# FPGA_Core.net
KiCad netlist of a schematic drawn in Altium Designer
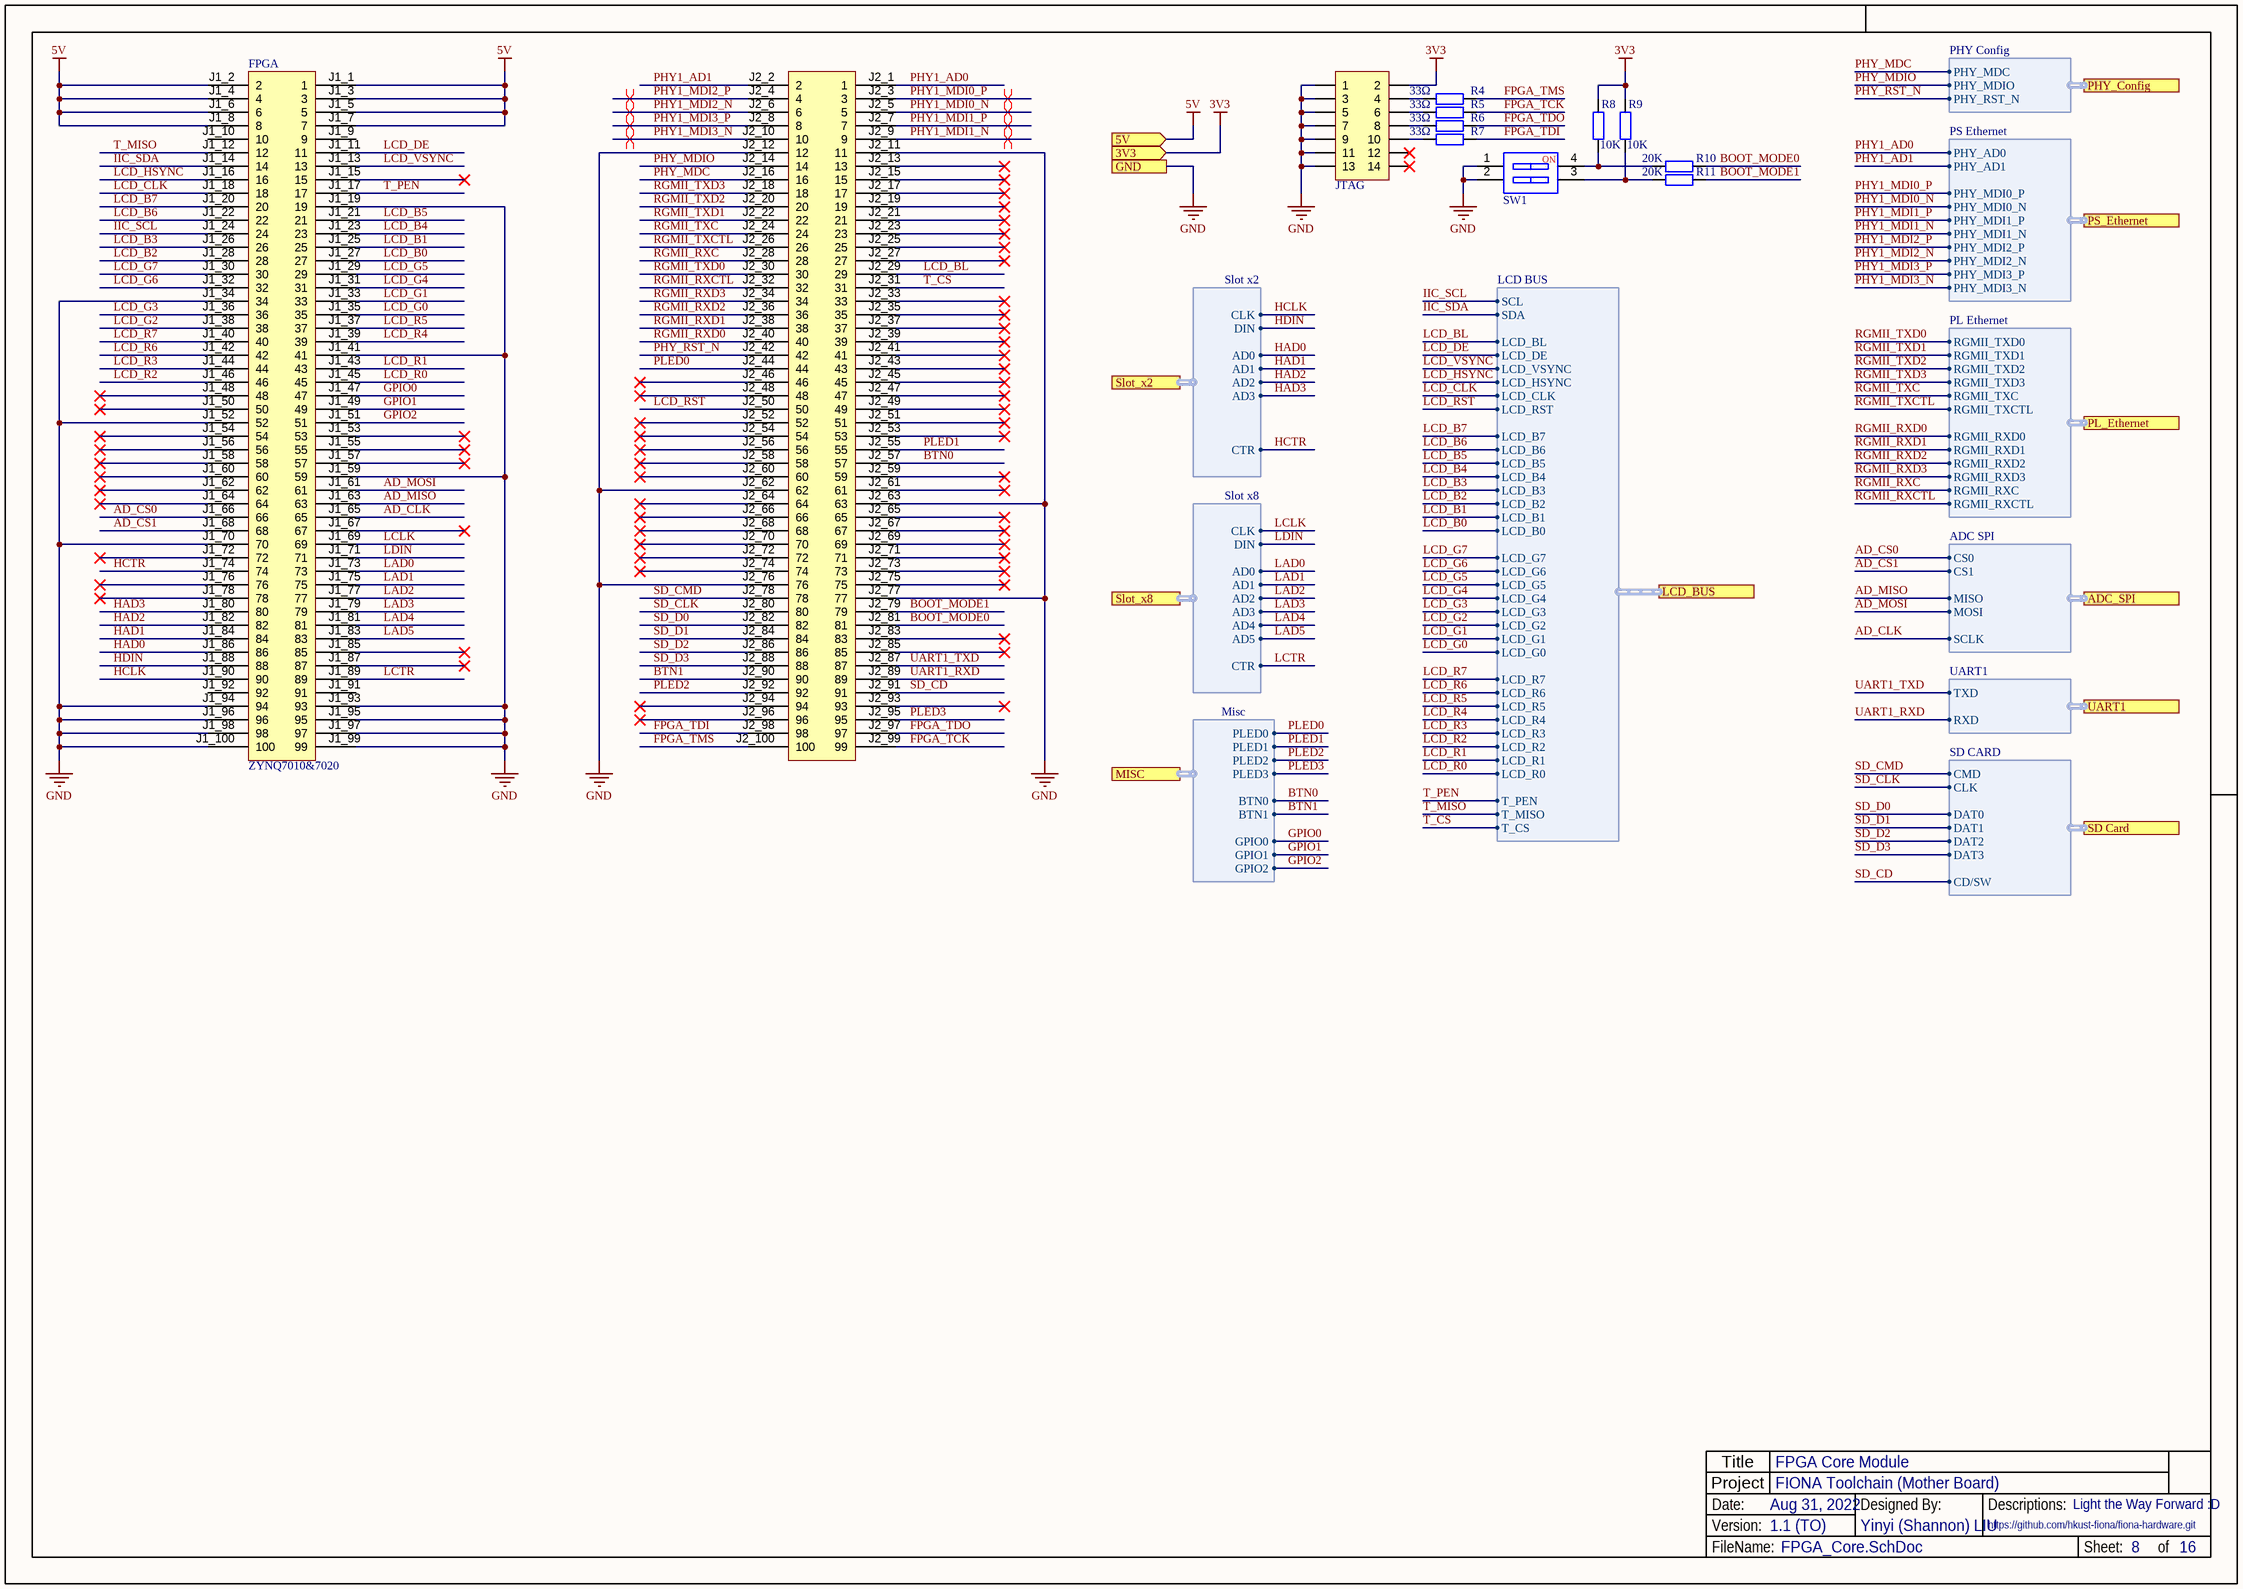
[diagram p0: FPGA_Core.SchDoc]

(export (version "E")
  (design (tool "Eeschema 10.0.6"))
  (components
    (comp (ref "FPGA")
      (value "ZYNQ7010&7020")
      (footprint "ZYNQ7010&7020_CB")
      (description "ZYNQ7010&7020 Core Board")
      (libsource (lib "领航者ZYNQ底板SCH&PCB封装库") (part "ZYNQ7010&7020"))
    )
    (comp (ref "JTAG")
      (value "Header 2X7")
      (footprint "IDC2.54-LI-2x7P")
      (description "7*2P接插件")
      (fields (field (name "版权归属") "封装库来自淘宝 ID：黄晶宝石"))
      (libsource (lib "5.4 - 接插件-脚距2.54 (100mil) ") (part "Header 7X2"))
    )
    (comp (ref "R4")
      (value "33Ω")
      (footprint "R 0603_L")
      (description "贴片电阻")
      (fields (field (name "版权归属") "来自淘宝 ID：黄晶宝石"))
      (libsource (lib "0.1 - 电阻-电容-电感") (part "R"))
    )
    (comp (ref "R5")
      (value "33Ω")
      (footprint "R 0603_L")
      (description "贴片电阻")
      (fields (field (name "版权归属") "来自淘宝 ID：黄晶宝石"))
      (libsource (lib "0.1 - 电阻-电容-电感") (part "R"))
    )
    (comp (ref "R6")
      (value "33Ω")
      (footprint "R 0603_L")
      (description "贴片电阻")
      (fields (field (name "版权归属") "来自淘宝 ID：黄晶宝石"))
      (libsource (lib "0.1 - 电阻-电容-电感") (part "R"))
    )
    (comp (ref "R7")
      (value "33Ω")
      (footprint "R 0603_L")
      (description "贴片电阻")
      (fields (field (name "版权归属") "来自淘宝 ID：黄晶宝石"))
      (libsource (lib "0.1 - 电阻-电容-电感") (part "R"))
    )
    (comp (ref "R8")
      (value "10K")
      (footprint "R 0603_L")
      (description "贴片电阻")
      (fields (field (name "版权归属") "来自淘宝 ID：黄晶宝石"))
      (libsource (lib "0.1 - 电阻-电容-电感") (part "R"))
    )
    (comp (ref "R9")
      (value "10K")
      (footprint "R 0603_L")
      (description "贴片电阻")
      (fields (field (name "版权归属") "来自淘宝 ID：黄晶宝石"))
      (libsource (lib "0.1 - 电阻-电容-电感") (part "R"))
    )
    (comp (ref "R10")
      (value "20K")
      (footprint "R 0603_L")
      (description "贴片电阻")
      (fields (field (name "版权归属") "来自淘宝 ID：黄晶宝石"))
      (libsource (lib "0.1 - 电阻-电容-电感") (part "R"))
    )
    (comp (ref "R11")
      (value "20K")
      (footprint "R 0603_L")
      (description "贴片电阻")
      (fields (field (name "版权归属") "来自淘宝 ID：黄晶宝石"))
      (libsource (lib "0.1 - 电阻-电容-电感") (part "R"))
    )
    (comp (ref "SW1")
      (value "SW-2P")
      (footprint "CSW DIP-2P")
      (description "2路编码开关\r\n*LCID: C976324")
      (libsource (lib "0.7 - 常用按键-开关") (part "SW-2P"))
    )
  )
  (nets
    (net (code "17") (name "/AD_CLK") (class "Default")
      (node (ref "FPGA") (pin "J1_65") (pinfunction "65_J1_65") (pintype "passive"))
    )
    (net (code "18") (name "/AD_CS0") (class "Default")
      (node (ref "FPGA") (pin "J1_66") (pinfunction "66_J1_66") (pintype "passive"))
    )
    (net (code "19") (name "/AD_CS1") (class "Default")
      (node (ref "FPGA") (pin "J1_68") (pinfunction "68_J1_68") (pintype "passive"))
    )
    (net (code "20") (name "/AD_MISO") (class "Default")
      (node (ref "FPGA") (pin "J1_63") (pinfunction "63_J1_63") (pintype "passive"))
    )
    (net (code "21") (name "/AD_MOSI") (class "Default")
      (node (ref "FPGA") (pin "J1_61") (pinfunction "61_J1_61") (pintype "passive"))
    )
    (net (code "22") (name "/BOOT_MODE0") (class "Default")
      (node (ref "FPGA") (pin "J2_81") (pinfunction "81_J2_81") (pintype "passive"))
      (node (ref "R10") (pin "2") (pinfunction "2_2") (pintype "passive"))
    )
    (net (code "23") (name "/BOOT_MODE1") (class "Default")
      (node (ref "FPGA") (pin "J2_79") (pinfunction "79_J2_79") (pintype "passive"))
      (node (ref "R11") (pin "2") (pinfunction "2_2") (pintype "passive"))
    )
    (net (code "24") (name "/BTN0") (class "Default")
      (node (ref "FPGA") (pin "J2_57") (pinfunction "57_J2_57") (pintype "passive"))
    )
    (net (code "25") (name "/BTN1") (class "Default")
      (node (ref "FPGA") (pin "J2_90") (pinfunction "90_J2_90") (pintype "passive"))
    )
    (net (code "26") (name "/FPGA_TCK") (class "Default")
      (node (ref "FPGA") (pin "J2_99") (pinfunction "99_J2_99") (pintype "passive"))
      (node (ref "R5") (pin "2") (pinfunction "2_2") (pintype "passive"))
    )
    (net (code "27") (name "/FPGA_TDI") (class "Default")
      (node (ref "FPGA") (pin "J2_98") (pinfunction "98_J2_98") (pintype "passive"))
      (node (ref "R7") (pin "2") (pinfunction "2_2") (pintype "passive"))
    )
    (net (code "28") (name "/FPGA_TDO") (class "Default")
      (node (ref "FPGA") (pin "J2_97") (pinfunction "97_J2_97") (pintype "passive"))
      (node (ref "R6") (pin "2") (pinfunction "2_2") (pintype "passive"))
    )
    (net (code "29") (name "/FPGA_TMS") (class "Default")
      (node (ref "FPGA") (pin "J2_100") (pinfunction "100_J2_100") (pintype "passive"))
      (node (ref "R4") (pin "2") (pinfunction "2_2") (pintype "passive"))
    )
    (net (code "30") (name "/GPIO0") (class "Default")
      (node (ref "FPGA") (pin "J1_47") (pinfunction "47_J1_47") (pintype "passive"))
    )
    (net (code "31") (name "/GPIO1") (class "Default")
      (node (ref "FPGA") (pin "J1_49") (pinfunction "49_J1_49") (pintype "passive"))
    )
    (net (code "32") (name "/GPIO2") (class "Default")
      (node (ref "FPGA") (pin "J1_51") (pinfunction "51_J1_51") (pintype "passive"))
    )
    (net (code "33") (name "/HAD0") (class "Default")
      (node (ref "FPGA") (pin "J1_86") (pinfunction "86_J1_86") (pintype "passive"))
    )
    (net (code "34") (name "/HAD1") (class "Default")
      (node (ref "FPGA") (pin "J1_84") (pinfunction "84_J1_84") (pintype "passive"))
    )
    (net (code "35") (name "/HAD2") (class "Default")
      (node (ref "FPGA") (pin "J1_82") (pinfunction "82_J1_82") (pintype "passive"))
    )
    (net (code "36") (name "/HAD3") (class "Default")
      (node (ref "FPGA") (pin "J1_80") (pinfunction "80_J1_80") (pintype "passive"))
    )
    (net (code "37") (name "/HCLK") (class "Default")
      (node (ref "FPGA") (pin "J1_90") (pinfunction "90_J1_90") (pintype "passive"))
    )
    (net (code "38") (name "/HCTR") (class "Default")
      (node (ref "FPGA") (pin "J1_74") (pinfunction "74_J1_74") (pintype "passive"))
    )
    (net (code "39") (name "/HDIN") (class "Default")
      (node (ref "FPGA") (pin "J1_88") (pinfunction "88_J1_88") (pintype "passive"))
    )
    (net (code "40") (name "/IIC_SCL") (class "Default")
      (node (ref "FPGA") (pin "J1_24") (pinfunction "24_J1_24") (pintype "passive"))
    )
    (net (code "41") (name "/IIC_SDA") (class "Default")
      (node (ref "FPGA") (pin "J1_14") (pinfunction "14_J1_14") (pintype "passive"))
    )
    (net (code "42") (name "/LAD0") (class "Default")
      (node (ref "FPGA") (pin "J1_73") (pinfunction "73_J1_73") (pintype "passive"))
    )
    (net (code "43") (name "/LAD1") (class "Default")
      (node (ref "FPGA") (pin "J1_75") (pinfunction "75_J1_75") (pintype "passive"))
    )
    (net (code "44") (name "/LAD2") (class "Default")
      (node (ref "FPGA") (pin "J1_77") (pinfunction "77_J1_77") (pintype "passive"))
    )
    (net (code "45") (name "/LAD3") (class "Default")
      (node (ref "FPGA") (pin "J1_79") (pinfunction "79_J1_79") (pintype "passive"))
    )
    (net (code "46") (name "/LAD4") (class "Default")
      (node (ref "FPGA") (pin "J1_81") (pinfunction "81_J1_81") (pintype "passive"))
    )
    (net (code "47") (name "/LAD5") (class "Default")
      (node (ref "FPGA") (pin "J1_83") (pinfunction "83_J1_83") (pintype "passive"))
    )
    (net (code "48") (name "/LCD_B0") (class "Default")
      (node (ref "FPGA") (pin "J1_27") (pinfunction "27_J1_27") (pintype "passive"))
    )
    (net (code "49") (name "/LCD_B1") (class "Default")
      (node (ref "FPGA") (pin "J1_25") (pinfunction "25_J1_25") (pintype "passive"))
    )
    (net (code "50") (name "/LCD_B2") (class "Default")
      (node (ref "FPGA") (pin "J1_28") (pinfunction "28_J1_28") (pintype "passive"))
    )
    (net (code "51") (name "/LCD_B3") (class "Default")
      (node (ref "FPGA") (pin "J1_26") (pinfunction "26_J1_26") (pintype "passive"))
    )
    (net (code "52") (name "/LCD_B4") (class "Default")
      (node (ref "FPGA") (pin "J1_23") (pinfunction "23_J1_23") (pintype "passive"))
    )
    (net (code "53") (name "/LCD_B5") (class "Default")
      (node (ref "FPGA") (pin "J1_21") (pinfunction "21_J1_21") (pintype "passive"))
    )
    (net (code "54") (name "/LCD_B6") (class "Default")
      (node (ref "FPGA") (pin "J1_22") (pinfunction "22_J1_22") (pintype "passive"))
    )
    (net (code "55") (name "/LCD_B7") (class "Default")
      (node (ref "FPGA") (pin "J1_20") (pinfunction "20_J1_20") (pintype "passive"))
    )
    (net (code "56") (name "/LCD_BL") (class "Default")
      (node (ref "FPGA") (pin "J2_29") (pinfunction "29_J2_29") (pintype "passive"))
    )
    (net (code "57") (name "/LCD_CLK") (class "Default")
      (node (ref "FPGA") (pin "J1_18") (pinfunction "18_J1_18") (pintype "passive"))
    )
    (net (code "58") (name "/LCD_DE") (class "Default")
      (node (ref "FPGA") (pin "J1_11") (pinfunction "11_J1_11") (pintype "passive"))
    )
    (net (code "59") (name "/LCD_G0") (class "Default")
      (node (ref "FPGA") (pin "J1_35") (pinfunction "35_J1_35") (pintype "passive"))
    )
    (net (code "60") (name "/LCD_G1") (class "Default")
      (node (ref "FPGA") (pin "J1_33") (pinfunction "33_J1_33") (pintype "passive"))
    )
    (net (code "61") (name "/LCD_G2") (class "Default")
      (node (ref "FPGA") (pin "J1_38") (pinfunction "38_J1_38") (pintype "passive"))
    )
    (net (code "62") (name "/LCD_G3") (class "Default")
      (node (ref "FPGA") (pin "J1_36") (pinfunction "36_J1_36") (pintype "passive"))
    )
    (net (code "63") (name "/LCD_G4") (class "Default")
      (node (ref "FPGA") (pin "J1_31") (pinfunction "31_J1_31") (pintype "passive"))
    )
    (net (code "64") (name "/LCD_G5") (class "Default")
      (node (ref "FPGA") (pin "J1_29") (pinfunction "29_J1_29") (pintype "passive"))
    )
    (net (code "65") (name "/LCD_G6") (class "Default")
      (node (ref "FPGA") (pin "J1_32") (pinfunction "32_J1_32") (pintype "passive"))
    )
    (net (code "66") (name "/LCD_G7") (class "Default")
      (node (ref "FPGA") (pin "J1_30") (pinfunction "30_J1_30") (pintype "passive"))
    )
    (net (code "67") (name "/LCD_HSYNC") (class "Default")
      (node (ref "FPGA") (pin "J1_16") (pinfunction "16_J1_16") (pintype "passive"))
    )
    (net (code "68") (name "/LCD_R0") (class "Default")
      (node (ref "FPGA") (pin "J1_45") (pinfunction "45_J1_45") (pintype "passive"))
    )
    (net (code "69") (name "/LCD_R1") (class "Default")
      (node (ref "FPGA") (pin "J1_43") (pinfunction "43_J1_43") (pintype "passive"))
    )
    (net (code "70") (name "/LCD_R2") (class "Default")
      (node (ref "FPGA") (pin "J1_46") (pinfunction "46_J1_46") (pintype "passive"))
    )
    (net (code "71") (name "/LCD_R3") (class "Default")
      (node (ref "FPGA") (pin "J1_44") (pinfunction "44_J1_44") (pintype "passive"))
    )
    (net (code "72") (name "/LCD_R4") (class "Default")
      (node (ref "FPGA") (pin "J1_39") (pinfunction "39_J1_39") (pintype "passive"))
    )
    (net (code "73") (name "/LCD_R5") (class "Default")
      (node (ref "FPGA") (pin "J1_37") (pinfunction "37_J1_37") (pintype "passive"))
    )
    (net (code "74") (name "/LCD_R6") (class "Default")
      (node (ref "FPGA") (pin "J1_42") (pinfunction "42_J1_42") (pintype "passive"))
    )
    (net (code "75") (name "/LCD_R7") (class "Default")
      (node (ref "FPGA") (pin "J1_40") (pinfunction "40_J1_40") (pintype "passive"))
    )
    (net (code "76") (name "/LCD_RST") (class "Default")
      (node (ref "FPGA") (pin "J2_50") (pinfunction "50_J2_50") (pintype "passive"))
    )
    (net (code "77") (name "/LCD_VSYNC") (class "Default")
      (node (ref "FPGA") (pin "J1_13") (pinfunction "13_J1_13") (pintype "passive"))
    )
    (net (code "78") (name "/LCLK") (class "Default")
      (node (ref "FPGA") (pin "J1_69") (pinfunction "69_J1_69") (pintype "passive"))
    )
    (net (code "79") (name "/LCTR") (class "Default")
      (node (ref "FPGA") (pin "J1_89") (pinfunction "89_J1_89") (pintype "passive"))
    )
    (net (code "80") (name "/LDIN") (class "Default")
      (node (ref "FPGA") (pin "J1_71") (pinfunction "71_J1_71") (pintype "passive"))
    )
    (net (code "81") (name "/PHY1_AD0") (class "Default")
      (node (ref "FPGA") (pin "J2_1") (pinfunction "1_J2_1") (pintype "passive"))
    )
    (net (code "82") (name "/PHY1_AD1") (class "Default")
      (node (ref "FPGA") (pin "J2_2") (pinfunction "2_J2_2") (pintype "passive"))
    )
    (net (code "83") (name "/PHY1_MDI0_N") (class "Default")
      (node (ref "FPGA") (pin "J2_5") (pinfunction "5_J2_5") (pintype "passive"))
    )
    (net (code "84") (name "/PHY1_MDI0_P") (class "Default")
      (node (ref "FPGA") (pin "J2_3") (pinfunction "3_J2_3") (pintype "passive"))
    )
    (net (code "85") (name "/PHY1_MDI1_N") (class "Default")
      (node (ref "FPGA") (pin "J2_9") (pinfunction "9_J2_9") (pintype "passive"))
    )
    (net (code "86") (name "/PHY1_MDI1_P") (class "Default")
      (node (ref "FPGA") (pin "J2_7") (pinfunction "7_J2_7") (pintype "passive"))
    )
    (net (code "87") (name "/PHY1_MDI2_N") (class "Default")
      (node (ref "FPGA") (pin "J2_6") (pinfunction "6_J2_6") (pintype "passive"))
    )
    (net (code "88") (name "/PHY1_MDI2_P") (class "Default")
      (node (ref "FPGA") (pin "J2_4") (pinfunction "4_J2_4") (pintype "passive"))
    )
    (net (code "89") (name "/PHY1_MDI3_N") (class "Default")
      (node (ref "FPGA") (pin "J2_10") (pinfunction "10_J2_10") (pintype "passive"))
    )
    (net (code "90") (name "/PHY1_MDI3_P") (class "Default")
      (node (ref "FPGA") (pin "J2_8") (pinfunction "8_J2_8") (pintype "passive"))
    )
    (net (code "91") (name "/PHY_MDC") (class "Default")
      (node (ref "FPGA") (pin "J2_16") (pinfunction "16_J2_16") (pintype "passive"))
    )
    (net (code "92") (name "/PHY_MDIO") (class "Default")
      (node (ref "FPGA") (pin "J2_14") (pinfunction "14_J2_14") (pintype "passive"))
    )
    (net (code "93") (name "/PHY_RST_N") (class "Default")
      (node (ref "FPGA") (pin "J2_42") (pinfunction "42_J2_42") (pintype "passive"))
    )
    (net (code "94") (name "/PLED0") (class "Default")
      (node (ref "FPGA") (pin "J2_44") (pinfunction "44_J2_44") (pintype "passive"))
    )
    (net (code "95") (name "/PLED1") (class "Default")
      (node (ref "FPGA") (pin "J2_55") (pinfunction "55_J2_55") (pintype "passive"))
    )
    (net (code "96") (name "/PLED2") (class "Default")
      (node (ref "FPGA") (pin "J2_92") (pinfunction "92_J2_92") (pintype "passive"))
    )
    (net (code "97") (name "/PLED3") (class "Default")
      (node (ref "FPGA") (pin "J2_95") (pinfunction "95_J2_95") (pintype "passive"))
    )
    (net (code "98") (name "/RGMII_RXC") (class "Default")
      (node (ref "FPGA") (pin "J2_28") (pinfunction "28_J2_28") (pintype "passive"))
    )
    (net (code "99") (name "/RGMII_RXCTL") (class "Default")
      (node (ref "FPGA") (pin "J2_32") (pinfunction "32_J2_32") (pintype "passive"))
    )
    (net (code "100") (name "/RGMII_RXD0") (class "Default")
      (node (ref "FPGA") (pin "J2_40") (pinfunction "40_J2_40") (pintype "passive"))
    )
    (net (code "101") (name "/RGMII_RXD1") (class "Default")
      (node (ref "FPGA") (pin "J2_38") (pinfunction "38_J2_38") (pintype "passive"))
    )
    (net (code "102") (name "/RGMII_RXD2") (class "Default")
      (node (ref "FPGA") (pin "J2_36") (pinfunction "36_J2_36") (pintype "passive"))
    )
    (net (code "103") (name "/RGMII_RXD3") (class "Default")
      (node (ref "FPGA") (pin "J2_34") (pinfunction "34_J2_34") (pintype "passive"))
    )
    (net (code "104") (name "/RGMII_TXC") (class "Default")
      (node (ref "FPGA") (pin "J2_24") (pinfunction "24_J2_24") (pintype "passive"))
    )
    (net (code "105") (name "/RGMII_TXCTL") (class "Default")
      (node (ref "FPGA") (pin "J2_26") (pinfunction "26_J2_26") (pintype "passive"))
    )
    (net (code "106") (name "/RGMII_TXD0") (class "Default")
      (node (ref "FPGA") (pin "J2_30") (pinfunction "30_J2_30") (pintype "passive"))
    )
    (net (code "107") (name "/RGMII_TXD1") (class "Default")
      (node (ref "FPGA") (pin "J2_22") (pinfunction "22_J2_22") (pintype "passive"))
    )
    (net (code "108") (name "/RGMII_TXD2") (class "Default")
      (node (ref "FPGA") (pin "J2_20") (pinfunction "20_J2_20") (pintype "passive"))
    )
    (net (code "109") (name "/RGMII_TXD3") (class "Default")
      (node (ref "FPGA") (pin "J2_18") (pinfunction "18_J2_18") (pintype "passive"))
    )
    (net (code "110") (name "/SD_CD") (class "Default")
      (node (ref "FPGA") (pin "J2_91") (pinfunction "91_J2_91") (pintype "passive"))
    )
    (net (code "111") (name "/SD_CLK") (class "Default")
      (node (ref "FPGA") (pin "J2_80") (pinfunction "80_J2_80") (pintype "passive"))
    )
    (net (code "112") (name "/SD_CMD") (class "Default")
      (node (ref "FPGA") (pin "J2_78") (pinfunction "78_J2_78") (pintype "passive"))
    )
    (net (code "113") (name "/SD_D0") (class "Default")
      (node (ref "FPGA") (pin "J2_82") (pinfunction "82_J2_82") (pintype "passive"))
    )
    (net (code "114") (name "/SD_D1") (class "Default")
      (node (ref "FPGA") (pin "J2_84") (pinfunction "84_J2_84") (pintype "passive"))
    )
    (net (code "115") (name "/SD_D2") (class "Default")
      (node (ref "FPGA") (pin "J2_86") (pinfunction "86_J2_86") (pintype "passive"))
    )
    (net (code "116") (name "/SD_D3") (class "Default")
      (node (ref "FPGA") (pin "J2_88") (pinfunction "88_J2_88") (pintype "passive"))
    )
    (net (code "117") (name "/T_CS") (class "Default")
      (node (ref "FPGA") (pin "J2_31") (pinfunction "31_J2_31") (pintype "passive"))
    )
    (net (code "118") (name "/T_MISO") (class "Default")
      (node (ref "FPGA") (pin "J1_12") (pinfunction "12_J1_12") (pintype "passive"))
    )
    (net (code "119") (name "/T_PEN") (class "Default")
      (node (ref "FPGA") (pin "J1_17") (pinfunction "17_J1_17") (pintype "passive"))
    )
    (net (code "120") (name "/UART1_RXD") (class "Default")
      (node (ref "FPGA") (pin "J2_89") (pinfunction "89_J2_89") (pintype "passive"))
    )
    (net (code "121") (name "/UART1_TXD") (class "Default")
      (node (ref "FPGA") (pin "J2_87") (pinfunction "87_J2_87") (pintype "passive"))
    )
    (net (code "132") (name "3V3") (class "Default")
      (node (ref "JTAG") (pin "2") (pinfunction "2_2") (pintype "passive"))
      (node (ref "R8") (pin "2") (pinfunction "2_2") (pintype "passive"))
      (node (ref "R9") (pin "2") (pinfunction "2_2") (pintype "passive"))
    )
    (net (code "133") (name "5V") (class "Default")
      (node (ref "FPGA") (pin "J1_1") (pinfunction "1_J1_1") (pintype "passive"))
      (node (ref "FPGA") (pin "J1_2") (pinfunction "2_J1_2") (pintype "passive"))
      (node (ref "FPGA") (pin "J1_3") (pinfunction "3_J1_3") (pintype "passive"))
      (node (ref "FPGA") (pin "J1_4") (pinfunction "4_J1_4") (pintype "passive"))
      (node (ref "FPGA") (pin "J1_5") (pinfunction "5_J1_5") (pintype "passive"))
      (node (ref "FPGA") (pin "J1_6") (pinfunction "6_J1_6") (pintype "passive"))
      (node (ref "FPGA") (pin "J1_7") (pinfunction "7_J1_7") (pintype "passive"))
      (node (ref "FPGA") (pin "J1_8") (pinfunction "8_J1_8") (pintype "passive"))
    )
    (net (code "134") (name "GND") (class "Default")
      (node (ref "FPGA") (pin "J1_100") (pinfunction "100_J1_100") (pintype "passive"))
      (node (ref "FPGA") (pin "J1_19") (pinfunction "19_J1_19") (pintype "passive"))
      (node (ref "FPGA") (pin "J1_34") (pinfunction "34_J1_34") (pintype "passive"))
      (node (ref "FPGA") (pin "J1_41") (pinfunction "41_J1_41") (pintype "passive"))
      (node (ref "FPGA") (pin "J1_52") (pinfunction "52_J1_52") (pintype "passive"))
      (node (ref "FPGA") (pin "J1_59") (pinfunction "59_J1_59") (pintype "passive"))
      (node (ref "FPGA") (pin "J1_70") (pinfunction "70_J1_70") (pintype "passive"))
      (node (ref "FPGA") (pin "J1_93") (pinfunction "93_J1_93") (pintype "passive"))
      (node (ref "FPGA") (pin "J1_94") (pinfunction "94_J1_94") (pintype "passive"))
      (node (ref "FPGA") (pin "J1_95") (pinfunction "95_J1_95") (pintype "passive"))
      (node (ref "FPGA") (pin "J1_96") (pinfunction "96_J1_96") (pintype "passive"))
      (node (ref "FPGA") (pin "J1_97") (pinfunction "97_J1_97") (pintype "passive"))
      (node (ref "FPGA") (pin "J1_98") (pinfunction "98_J1_98") (pintype "passive"))
      (node (ref "FPGA") (pin "J1_99") (pinfunction "99_J1_99") (pintype "passive"))
      (node (ref "FPGA") (pin "J2_11") (pinfunction "11_J2_11") (pintype "passive"))
      (node (ref "FPGA") (pin "J2_12") (pinfunction "12_J2_12") (pintype "passive"))
      (node (ref "FPGA") (pin "J2_62") (pinfunction "62_J2_62") (pintype "passive"))
      (node (ref "FPGA") (pin "J2_63") (pinfunction "63_J2_63") (pintype "passive"))
      (node (ref "FPGA") (pin "J2_76") (pinfunction "76_J2_76") (pintype "passive"))
      (node (ref "FPGA") (pin "J2_77") (pinfunction "77_J2_77") (pintype "passive"))
      (node (ref "JTAG") (pin "1") (pinfunction "1_1") (pintype "passive"))
      (node (ref "JTAG") (pin "11") (pinfunction "11_11") (pintype "passive"))
      (node (ref "JTAG") (pin "13") (pinfunction "13_13") (pintype "passive"))
      (node (ref "JTAG") (pin "3") (pinfunction "3_3") (pintype "passive"))
      (node (ref "JTAG") (pin "5") (pinfunction "5_5") (pintype "passive"))
      (node (ref "JTAG") (pin "7") (pinfunction "7_7") (pintype "passive"))
      (node (ref "JTAG") (pin "9") (pinfunction "9_9") (pintype "passive"))
      (node (ref "SW1") (pin "1") (pinfunction "1_1") (pintype "passive"))
      (node (ref "SW1") (pin "2") (pinfunction "2_2") (pintype "passive"))
    )
    (net (code "135") (name "Net-(JTAG-Pad4)") (class "Default")
      (node (ref "JTAG") (pin "4") (pinfunction "4_4") (pintype "passive"))
      (node (ref "R4") (pin "1") (pinfunction "1_1") (pintype "passive"))
    )
    (net (code "136") (name "Net-(JTAG-Pad6)") (class "Default")
      (node (ref "JTAG") (pin "6") (pinfunction "6_6") (pintype "passive"))
      (node (ref "R5") (pin "1") (pinfunction "1_1") (pintype "passive"))
    )
    (net (code "137") (name "Net-(JTAG-Pad8)") (class "Default")
      (node (ref "JTAG") (pin "8") (pinfunction "8_8") (pintype "passive"))
      (node (ref "R6") (pin "1") (pinfunction "1_1") (pintype "passive"))
    )
    (net (code "138") (name "Net-(JTAG-Pad10)") (class "Default")
      (node (ref "JTAG") (pin "10") (pinfunction "10_10") (pintype "passive"))
      (node (ref "R7") (pin "1") (pinfunction "1_1") (pintype "passive"))
    )
    (net (code "139") (name "Net-(R10-Pad1)") (class "Default")
      (node (ref "R10") (pin "1") (pinfunction "1_1") (pintype "passive"))
      (node (ref "R8") (pin "1") (pinfunction "1_1") (pintype "passive"))
      (node (ref "SW1") (pin "4") (pinfunction "4_4") (pintype "passive"))
    )
    (net (code "140") (name "Net-(R11-Pad1)") (class "Default")
      (node (ref "R11") (pin "1") (pinfunction "1_1") (pintype "passive"))
      (node (ref "R9") (pin "1") (pinfunction "1_1") (pintype "passive"))
      (node (ref "SW1") (pin "3") (pinfunction "3_3") (pintype "passive"))
    )
    (net (code "141") (name "unconnected-(FPGA-9-PadJ1_9)") (class "Default")
      (node (ref "FPGA") (pin "J1_9") (pinfunction "9_J1_9") (pintype "passive"))
    )
    (net (code "142") (name "unconnected-(FPGA-10-PadJ1_10)") (class "Default")
      (node (ref "FPGA") (pin "J1_10") (pinfunction "10_J1_10") (pintype "passive"))
    )
    (net (code "143") (name "unconnected-(FPGA-13-PadJ2_13)") (class "Default")
      (node (ref "FPGA") (pin "J2_13") (pinfunction "13_J2_13") (pintype "passive+no_connect"))
    )
    (net (code "144") (name "unconnected-(FPGA-15-PadJ1_15)") (class "Default")
      (node (ref "FPGA") (pin "J1_15") (pinfunction "15_J1_15") (pintype "passive+no_connect"))
    )
    (net (code "145") (name "unconnected-(FPGA-15-PadJ2_15)") (class "Default")
      (node (ref "FPGA") (pin "J2_15") (pinfunction "15_J2_15") (pintype "passive+no_connect"))
    )
    (net (code "146") (name "unconnected-(FPGA-17-PadJ2_17)") (class "Default")
      (node (ref "FPGA") (pin "J2_17") (pinfunction "17_J2_17") (pintype "passive+no_connect"))
    )
    (net (code "147") (name "unconnected-(FPGA-19-PadJ2_19)") (class "Default")
      (node (ref "FPGA") (pin "J2_19") (pinfunction "19_J2_19") (pintype "passive+no_connect"))
    )
    (net (code "148") (name "unconnected-(FPGA-21-PadJ2_21)") (class "Default")
      (node (ref "FPGA") (pin "J2_21") (pinfunction "21_J2_21") (pintype "passive+no_connect"))
    )
    (net (code "149") (name "unconnected-(FPGA-23-PadJ2_23)") (class "Default")
      (node (ref "FPGA") (pin "J2_23") (pinfunction "23_J2_23") (pintype "passive+no_connect"))
    )
    (net (code "150") (name "unconnected-(FPGA-25-PadJ2_25)") (class "Default")
      (node (ref "FPGA") (pin "J2_25") (pinfunction "25_J2_25") (pintype "passive+no_connect"))
    )
    (net (code "151") (name "unconnected-(FPGA-27-PadJ2_27)") (class "Default")
      (node (ref "FPGA") (pin "J2_27") (pinfunction "27_J2_27") (pintype "passive+no_connect"))
    )
    (net (code "152") (name "unconnected-(FPGA-33-PadJ2_33)") (class "Default")
      (node (ref "FPGA") (pin "J2_33") (pinfunction "33_J2_33") (pintype "passive+no_connect"))
    )
    (net (code "153") (name "unconnected-(FPGA-35-PadJ2_35)") (class "Default")
      (node (ref "FPGA") (pin "J2_35") (pinfunction "35_J2_35") (pintype "passive+no_connect"))
    )
    (net (code "154") (name "unconnected-(FPGA-37-PadJ2_37)") (class "Default")
      (node (ref "FPGA") (pin "J2_37") (pinfunction "37_J2_37") (pintype "passive+no_connect"))
    )
    (net (code "155") (name "unconnected-(FPGA-39-PadJ2_39)") (class "Default")
      (node (ref "FPGA") (pin "J2_39") (pinfunction "39_J2_39") (pintype "passive+no_connect"))
    )
    (net (code "156") (name "unconnected-(FPGA-41-PadJ2_41)") (class "Default")
      (node (ref "FPGA") (pin "J2_41") (pinfunction "41_J2_41") (pintype "passive+no_connect"))
    )
    (net (code "157") (name "unconnected-(FPGA-43-PadJ2_43)") (class "Default")
      (node (ref "FPGA") (pin "J2_43") (pinfunction "43_J2_43") (pintype "passive+no_connect"))
    )
    (net (code "158") (name "unconnected-(FPGA-45-PadJ2_45)") (class "Default")
      (node (ref "FPGA") (pin "J2_45") (pinfunction "45_J2_45") (pintype "passive+no_connect"))
    )
    (net (code "159") (name "unconnected-(FPGA-46-PadJ2_46)") (class "Default")
      (node (ref "FPGA") (pin "J2_46") (pinfunction "46_J2_46") (pintype "passive+no_connect"))
    )
    (net (code "160") (name "unconnected-(FPGA-47-PadJ2_47)") (class "Default")
      (node (ref "FPGA") (pin "J2_47") (pinfunction "47_J2_47") (pintype "passive+no_connect"))
    )
    (net (code "161") (name "unconnected-(FPGA-48-PadJ1_48)") (class "Default")
      (node (ref "FPGA") (pin "J1_48") (pinfunction "48_J1_48") (pintype "passive+no_connect"))
    )
    (net (code "162") (name "unconnected-(FPGA-48-PadJ2_48)") (class "Default")
      (node (ref "FPGA") (pin "J2_48") (pinfunction "48_J2_48") (pintype "passive+no_connect"))
    )
    (net (code "163") (name "unconnected-(FPGA-49-PadJ2_49)") (class "Default")
      (node (ref "FPGA") (pin "J2_49") (pinfunction "49_J2_49") (pintype "passive+no_connect"))
    )
    (net (code "164") (name "unconnected-(FPGA-50-PadJ1_50)") (class "Default")
      (node (ref "FPGA") (pin "J1_50") (pinfunction "50_J1_50") (pintype "passive+no_connect"))
    )
    (net (code "165") (name "unconnected-(FPGA-51-PadJ2_51)") (class "Default")
      (node (ref "FPGA") (pin "J2_51") (pinfunction "51_J2_51") (pintype "passive+no_connect"))
    )
    (net (code "166") (name "unconnected-(FPGA-52-PadJ2_52)") (class "Default")
      (node (ref "FPGA") (pin "J2_52") (pinfunction "52_J2_52") (pintype "passive+no_connect"))
    )
    (net (code "167") (name "unconnected-(FPGA-53-PadJ1_53)") (class "Default")
      (node (ref "FPGA") (pin "J1_53") (pinfunction "53_J1_53") (pintype "passive+no_connect"))
    )
    (net (code "168") (name "unconnected-(FPGA-53-PadJ2_53)") (class "Default")
      (node (ref "FPGA") (pin "J2_53") (pinfunction "53_J2_53") (pintype "passive+no_connect"))
    )
    (net (code "169") (name "unconnected-(FPGA-54-PadJ1_54)") (class "Default")
      (node (ref "FPGA") (pin "J1_54") (pinfunction "54_J1_54") (pintype "passive+no_connect"))
    )
    (net (code "170") (name "unconnected-(FPGA-54-PadJ2_54)") (class "Default")
      (node (ref "FPGA") (pin "J2_54") (pinfunction "54_J2_54") (pintype "passive+no_connect"))
    )
    (net (code "171") (name "unconnected-(FPGA-55-PadJ1_55)") (class "Default")
      (node (ref "FPGA") (pin "J1_55") (pinfunction "55_J1_55") (pintype "passive+no_connect"))
    )
    (net (code "172") (name "unconnected-(FPGA-56-PadJ1_56)") (class "Default")
      (node (ref "FPGA") (pin "J1_56") (pinfunction "56_J1_56") (pintype "passive+no_connect"))
    )
    (net (code "173") (name "unconnected-(FPGA-56-PadJ2_56)") (class "Default")
      (node (ref "FPGA") (pin "J2_56") (pinfunction "56_J2_56") (pintype "passive+no_connect"))
    )
    (net (code "174") (name "unconnected-(FPGA-57-PadJ1_57)") (class "Default")
      (node (ref "FPGA") (pin "J1_57") (pinfunction "57_J1_57") (pintype "passive+no_connect"))
    )
    (net (code "175") (name "unconnected-(FPGA-58-PadJ1_58)") (class "Default")
      (node (ref "FPGA") (pin "J1_58") (pinfunction "58_J1_58") (pintype "passive+no_connect"))
    )
    (net (code "176") (name "unconnected-(FPGA-58-PadJ2_58)") (class "Default")
      (node (ref "FPGA") (pin "J2_58") (pinfunction "58_J2_58") (pintype "passive+no_connect"))
    )
    (net (code "177") (name "unconnected-(FPGA-59-PadJ2_59)") (class "Default")
      (node (ref "FPGA") (pin "J2_59") (pinfunction "59_J2_59") (pintype "passive+no_connect"))
    )
    (net (code "178") (name "unconnected-(FPGA-60-PadJ1_60)") (class "Default")
      (node (ref "FPGA") (pin "J1_60") (pinfunction "60_J1_60") (pintype "passive+no_connect"))
    )
    (net (code "179") (name "unconnected-(FPGA-60-PadJ2_60)") (class "Default")
      (node (ref "FPGA") (pin "J2_60") (pinfunction "60_J2_60") (pintype "passive+no_connect"))
    )
    (net (code "180") (name "unconnected-(FPGA-61-PadJ2_61)") (class "Default")
      (node (ref "FPGA") (pin "J2_61") (pinfunction "61_J2_61") (pintype "passive+no_connect"))
    )
    (net (code "181") (name "unconnected-(FPGA-62-PadJ1_62)") (class "Default")
      (node (ref "FPGA") (pin "J1_62") (pinfunction "62_J1_62") (pintype "passive+no_connect"))
    )
    (net (code "182") (name "unconnected-(FPGA-64-PadJ1_64)") (class "Default")
      (node (ref "FPGA") (pin "J1_64") (pinfunction "64_J1_64") (pintype "passive+no_connect"))
    )
    (net (code "183") (name "unconnected-(FPGA-64-PadJ2_64)") (class "Default")
      (node (ref "FPGA") (pin "J2_64") (pinfunction "64_J2_64") (pintype "passive+no_connect"))
    )
    (net (code "184") (name "unconnected-(FPGA-65-PadJ2_65)") (class "Default")
      (node (ref "FPGA") (pin "J2_65") (pinfunction "65_J2_65") (pintype "passive+no_connect"))
    )
    (net (code "185") (name "unconnected-(FPGA-66-PadJ2_66)") (class "Default")
      (node (ref "FPGA") (pin "J2_66") (pinfunction "66_J2_66") (pintype "passive+no_connect"))
    )
    (net (code "186") (name "unconnected-(FPGA-67-PadJ1_67)") (class "Default")
      (node (ref "FPGA") (pin "J1_67") (pinfunction "67_J1_67") (pintype "passive+no_connect"))
    )
    (net (code "187") (name "unconnected-(FPGA-67-PadJ2_67)") (class "Default")
      (node (ref "FPGA") (pin "J2_67") (pinfunction "67_J2_67") (pintype "passive+no_connect"))
    )
    (net (code "188") (name "unconnected-(FPGA-68-PadJ2_68)") (class "Default")
      (node (ref "FPGA") (pin "J2_68") (pinfunction "68_J2_68") (pintype "passive+no_connect"))
    )
    (net (code "189") (name "unconnected-(FPGA-69-PadJ2_69)") (class "Default")
      (node (ref "FPGA") (pin "J2_69") (pinfunction "69_J2_69") (pintype "passive+no_connect"))
    )
    (net (code "190") (name "unconnected-(FPGA-70-PadJ2_70)") (class "Default")
      (node (ref "FPGA") (pin "J2_70") (pinfunction "70_J2_70") (pintype "passive+no_connect"))
    )
    (net (code "191") (name "unconnected-(FPGA-71-PadJ2_71)") (class "Default")
      (node (ref "FPGA") (pin "J2_71") (pinfunction "71_J2_71") (pintype "passive+no_connect"))
    )
    (net (code "192") (name "unconnected-(FPGA-72-PadJ1_72)") (class "Default")
      (node (ref "FPGA") (pin "J1_72") (pinfunction "72_J1_72") (pintype "passive+no_connect"))
    )
    (net (code "193") (name "unconnected-(FPGA-72-PadJ2_72)") (class "Default")
      (node (ref "FPGA") (pin "J2_72") (pinfunction "72_J2_72") (pintype "passive+no_connect"))
    )
    (net (code "194") (name "unconnected-(FPGA-73-PadJ2_73)") (class "Default")
      (node (ref "FPGA") (pin "J2_73") (pinfunction "73_J2_73") (pintype "passive+no_connect"))
    )
    (net (code "195") (name "unconnected-(FPGA-74-PadJ2_74)") (class "Default")
      (node (ref "FPGA") (pin "J2_74") (pinfunction "74_J2_74") (pintype "passive+no_connect"))
    )
    (net (code "196") (name "unconnected-(FPGA-75-PadJ2_75)") (class "Default")
      (node (ref "FPGA") (pin "J2_75") (pinfunction "75_J2_75") (pintype "passive+no_connect"))
    )
    (net (code "197") (name "unconnected-(FPGA-76-PadJ1_76)") (class "Default")
      (node (ref "FPGA") (pin "J1_76") (pinfunction "76_J1_76") (pintype "passive+no_connect"))
    )
    (net (code "198") (name "unconnected-(FPGA-78-PadJ1_78)") (class "Default")
      (node (ref "FPGA") (pin "J1_78") (pinfunction "78_J1_78") (pintype "passive+no_connect"))
    )
    (net (code "199") (name "unconnected-(FPGA-83-PadJ2_83)") (class "Default")
      (node (ref "FPGA") (pin "J2_83") (pinfunction "83_J2_83") (pintype "passive+no_connect"))
    )
    (net (code "200") (name "unconnected-(FPGA-85-PadJ1_85)") (class "Default")
      (node (ref "FPGA") (pin "J1_85") (pinfunction "85_J1_85") (pintype "passive+no_connect"))
    )
    (net (code "201") (name "unconnected-(FPGA-85-PadJ2_85)") (class "Default")
      (node (ref "FPGA") (pin "J2_85") (pinfunction "85_J2_85") (pintype "passive+no_connect"))
    )
    (net (code "202") (name "unconnected-(FPGA-87-PadJ1_87)") (class "Default")
      (node (ref "FPGA") (pin "J1_87") (pinfunction "87_J1_87") (pintype "passive+no_connect"))
    )
    (net (code "203") (name "unconnected-(FPGA-91-PadJ1_91)") (class "Default")
      (node (ref "FPGA") (pin "J1_91") (pinfunction "91_J1_91") (pintype "passive"))
    )
    (net (code "204") (name "unconnected-(FPGA-92-PadJ1_92)") (class "Default")
      (node (ref "FPGA") (pin "J1_92") (pinfunction "92_J1_92") (pintype "passive"))
    )
    (net (code "205") (name "unconnected-(FPGA-93-PadJ2_93)") (class "Default")
      (node (ref "FPGA") (pin "J2_93") (pinfunction "93_J2_93") (pintype "passive+no_connect"))
    )
    (net (code "206") (name "unconnected-(FPGA-94-PadJ2_94)") (class "Default")
      (node (ref "FPGA") (pin "J2_94") (pinfunction "94_J2_94") (pintype "passive+no_connect"))
    )
    (net (code "207") (name "unconnected-(FPGA-96-PadJ2_96)") (class "Default")
      (node (ref "FPGA") (pin "J2_96") (pinfunction "96_J2_96") (pintype "passive+no_connect"))
    )
    (net (code "208") (name "unconnected-(JTAG-Pad12)") (class "Default")
      (node (ref "JTAG") (pin "12") (pinfunction "12_12") (pintype "passive+no_connect"))
    )
    (net (code "209") (name "unconnected-(JTAG-Pad14)") (class "Default")
      (node (ref "JTAG") (pin "14") (pinfunction "14_14") (pintype "passive+no_connect"))
    )
  )
)
